# FSP.net
KiCad netlist of a schematic drawn in Altium Designer
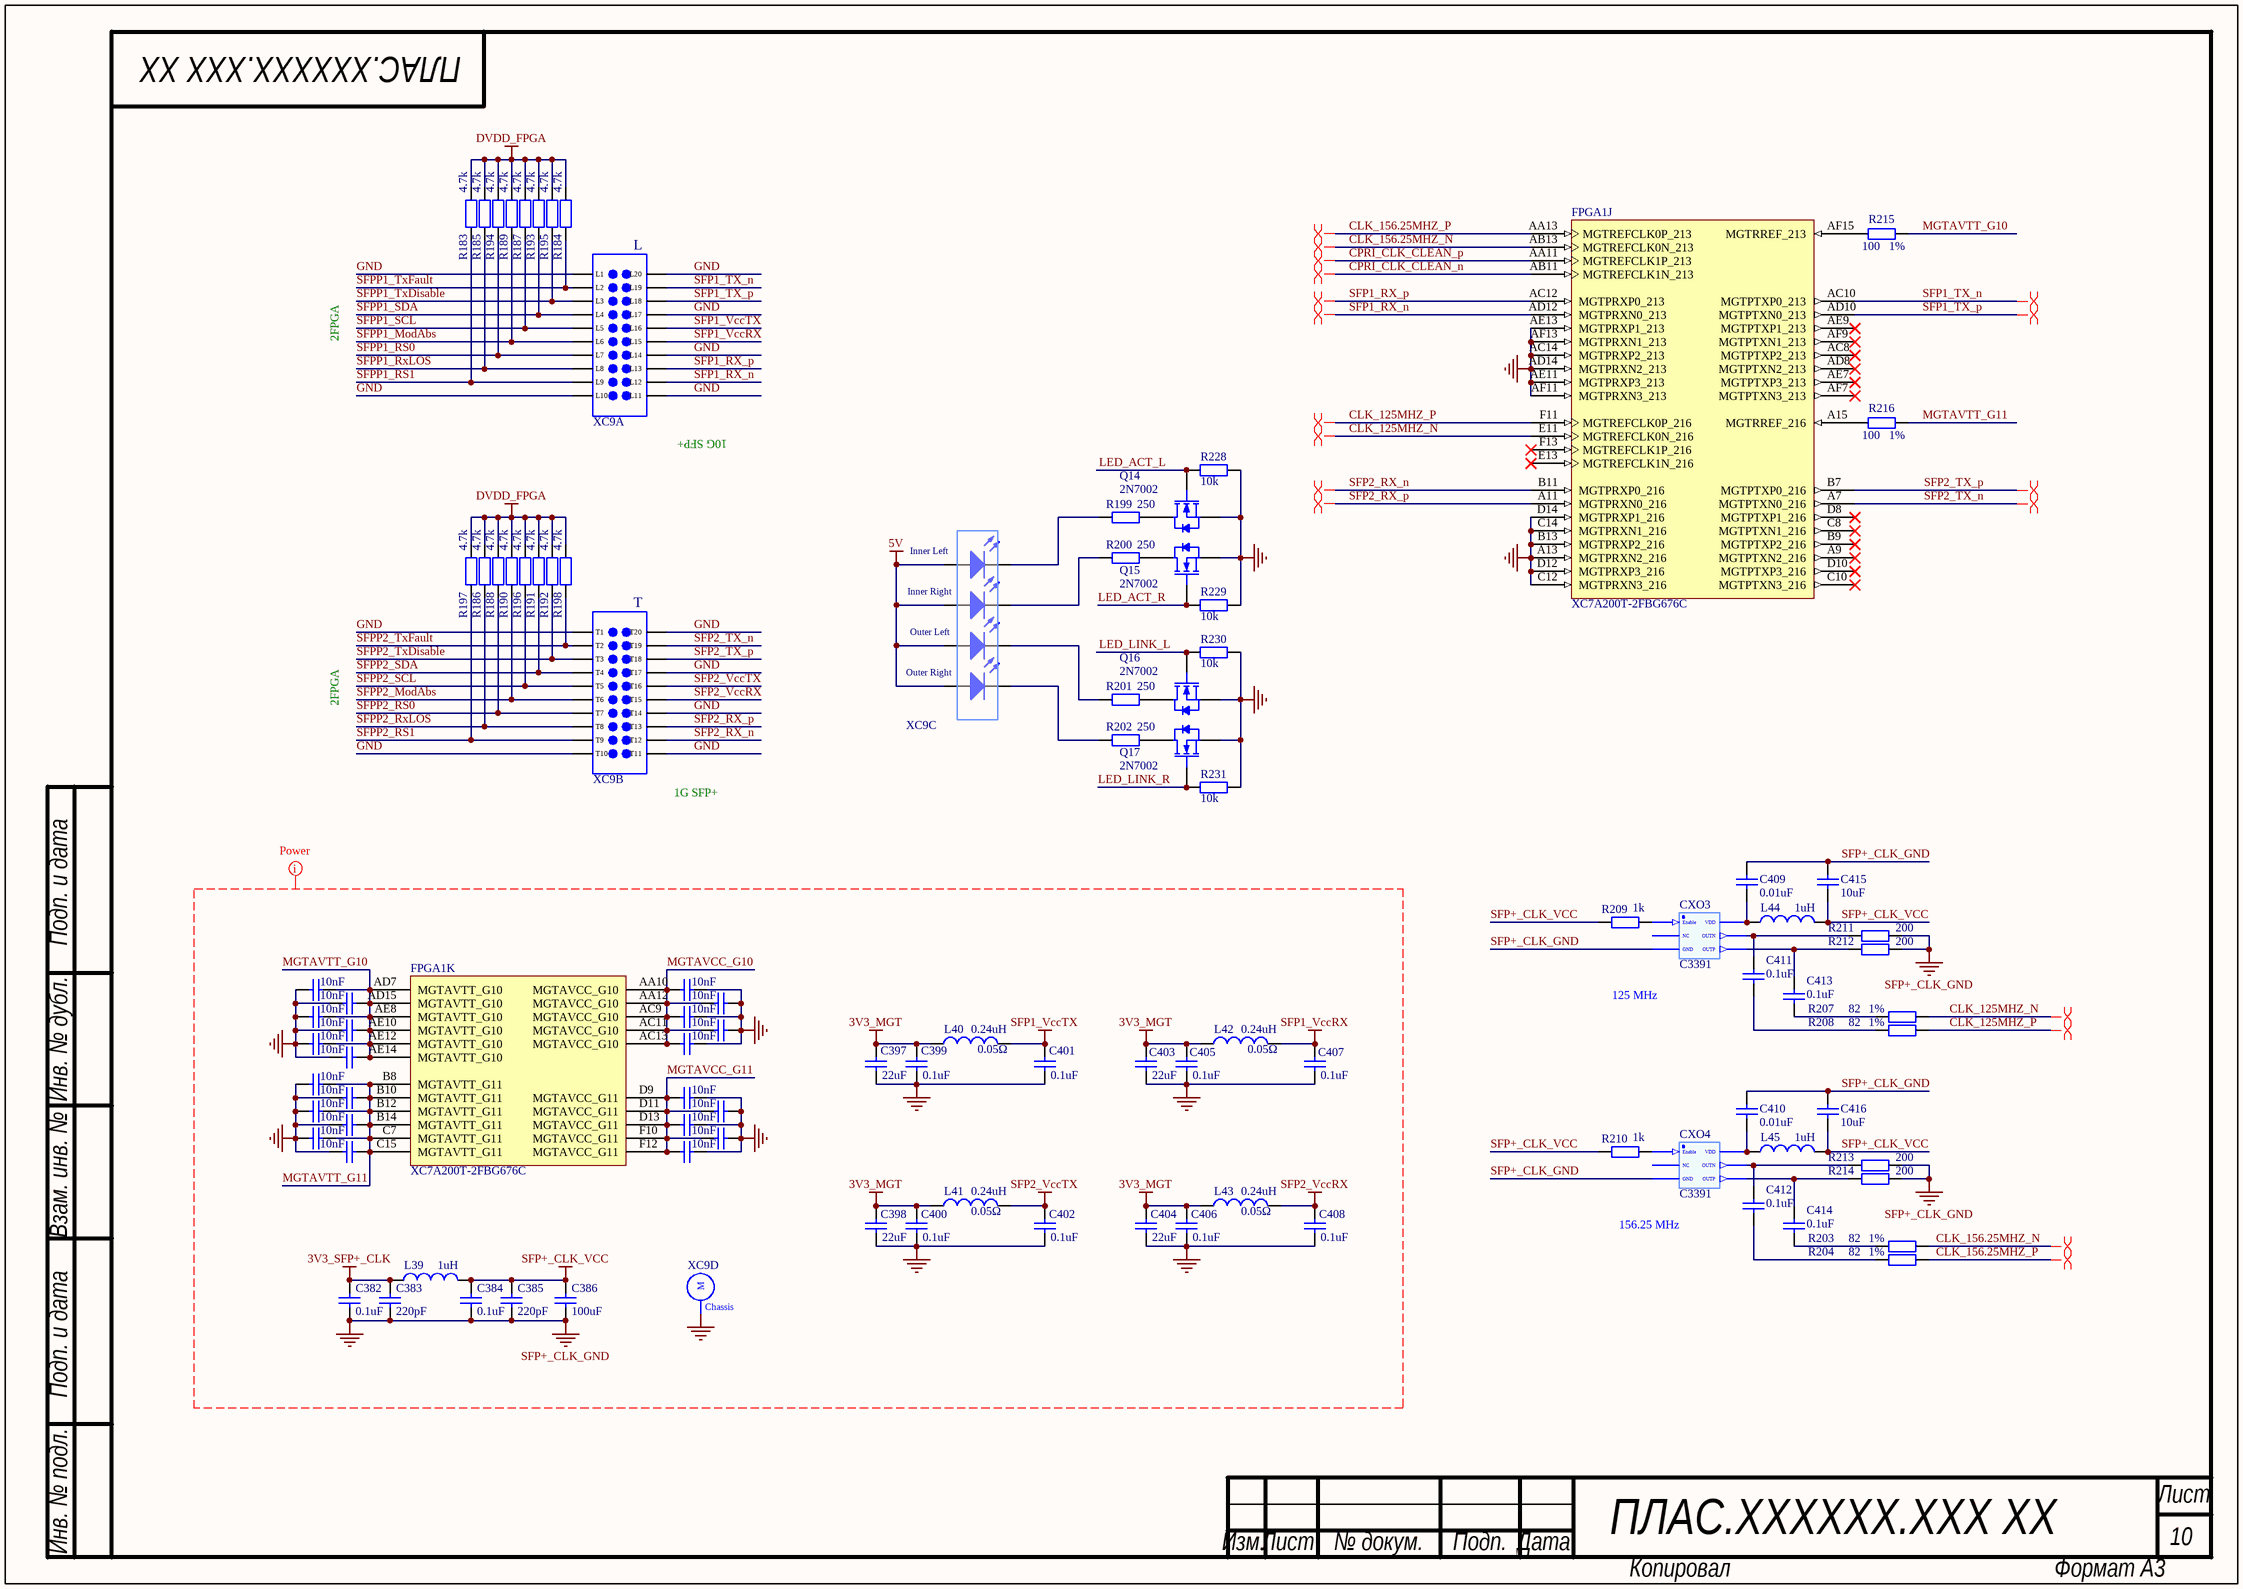
[diagram p0: FSP+.SchDoc]

(export (version "E")
  (design (tool "Eeschema 10.0.6"))
  (components
    (comp (ref "C370")
      (value "10nF")
      (footprint "С0402")
      (description "Cer Cap Small")
      (fields (field (name "MANUFACTURER") "Murata") (field (name "VOLTAGE") "25V"))
      (libsource (lib "") (part "Cer Cap_1"))
    )
    (comp (ref "C371")
      (value "10nF")
      (footprint "С0402")
      (description "Cer Cap Small")
      (fields (field (name "MANUFACTURER") "Murata") (field (name "VOLTAGE") "25V"))
      (libsource (lib "USRP2_Clone") (part "Cer Cap"))
    )
    (comp (ref "C372")
      (value "10nF")
      (footprint "С0402")
      (description "Cer Cap Small")
      (fields (field (name "MANUFACTURER") "Murata") (field (name "VOLTAGE") "25V"))
      (libsource (lib "USRP2_Clone") (part "Cer Cap"))
    )
    (comp (ref "C373")
      (value "10nF")
      (footprint "С0402")
      (description "Cer Cap Small")
      (fields (field (name "MANUFACTURER") "Murata") (field (name "VOLTAGE") "25V"))
      (libsource (lib "") (part "Cer Cap_1"))
    )
    (comp (ref "C374")
      (value "10nF")
      (footprint "С0402")
      (description "Cer Cap Small")
      (fields (field (name "MANUFACTURER") "Murata") (field (name "VOLTAGE") "25V"))
      (libsource (lib "") (part "Cer Cap_1"))
    )
    (comp (ref "C375")
      (value "10nF")
      (footprint "С0402")
      (description "Cer Cap Small")
      (fields (field (name "MANUFACTURER") "Murata") (field (name "VOLTAGE") "25V"))
      (libsource (lib "") (part "Cer Cap_1"))
    )
    (comp (ref "C376")
      (value "10nF")
      (footprint "С0402")
      (description "Cer Cap Small")
      (fields (field (name "MANUFACTURER") "Murata") (field (name "VOLTAGE") "25V"))
      (libsource (lib "") (part "Cer Cap_1"))
    )
    (comp (ref "C377")
      (value "10nF")
      (footprint "С0402")
      (description "Cer Cap Small")
      (fields (field (name "MANUFACTURER") "Murata") (field (name "VOLTAGE") "25V"))
      (libsource (lib "") (part "Cer Cap_1"))
    )
    (comp (ref "C378")
      (value "10nF")
      (footprint "С0402")
      (description "Cer Cap Small")
      (fields (field (name "MANUFACTURER") "Murata") (field (name "VOLTAGE") "25V"))
      (libsource (lib "") (part "Cer Cap_1"))
    )
    (comp (ref "C379")
      (value "10nF")
      (footprint "С0402")
      (description "Cer Cap Small")
      (fields (field (name "MANUFACTURER") "Murata") (field (name "VOLTAGE") "25V"))
      (libsource (lib "USRP2_Clone") (part "Cer Cap"))
    )
    (comp (ref "C380")
      (value "10nF")
      (footprint "С0402")
      (description "Cer Cap Small")
      (fields (field (name "MANUFACTURER") "Murata") (field (name "VOLTAGE") "25V"))
      (libsource (lib "USRP2_Clone") (part "Cer Cap"))
    )
    (comp (ref "C381")
      (value "10nF")
      (footprint "С0402")
      (description "Cer Cap Small")
      (fields (field (name "MANUFACTURER") "Murata") (field (name "VOLTAGE") "25V"))
      (libsource (lib "") (part "Cer Cap_1"))
    )
    (comp (ref "C382")
      (value "0.1uF")
      (footprint "C0603")
      (description "Cer Cap Small")
      (fields (field (name "MANUFACTURER") "Murata") (field (name "VOLTAGE") "16V"))
      (libsource (lib "USRP2_Clone") (part "Cer Cap"))
    )
    (comp (ref "C383")
      (value "220pF")
      (footprint "C0603")
      (description "Cer Cap Small")
      (fields (field (name "MANUFACTURER") "Murata") (field (name "VOLTAGE") "16V"))
      (libsource (lib "USRP2_Clone") (part "Cer Cap"))
    )
    (comp (ref "C384")
      (value "0.1uF")
      (footprint "C0603")
      (description "Cer Cap Small")
      (fields (field (name "MANUFACTURER") "Murata") (field (name "VOLTAGE") "16V"))
      (libsource (lib "USRP2_Clone") (part "Cer Cap"))
    )
    (comp (ref "C385")
      (value "220pF")
      (footprint "C0603")
      (description "Cer Cap Small")
      (fields (field (name "MANUFACTURER") "Murata") (field (name "VOLTAGE") "16V"))
      (libsource (lib "USRP2_Clone") (part "Cer Cap"))
    )
    (comp (ref "C386")
      (value "100uF")
      (footprint "C1210")
      (description "Cer Cap Large")
      (fields (field (name "MANUFACTURER") "Murata") (field (name "TOLERANCE") "20%"))
      (libsource (lib "USRP2_Clone") (part "Cap uF"))
    )
    (comp (ref "C387")
      (value "10nF")
      (footprint "С0402")
      (description "Cer Cap Small")
      (fields (field (name "MANUFACTURER") "Murata") (field (name "VOLTAGE") "25V"))
      (libsource (lib "") (part "Cer Cap_1"))
    )
    (comp (ref "C388")
      (value "10nF")
      (footprint "С0402")
      (description "Cer Cap Small")
      (fields (field (name "MANUFACTURER") "Murata") (field (name "VOLTAGE") "25V"))
      (libsource (lib "USRP2_Clone") (part "Cer Cap"))
    )
    (comp (ref "C389")
      (value "10nF")
      (footprint "С0402")
      (description "Cer Cap Small")
      (fields (field (name "MANUFACTURER") "Murata") (field (name "VOLTAGE") "25V"))
      (libsource (lib "") (part "Cer Cap_1"))
    )
    (comp (ref "C390")
      (value "10nF")
      (footprint "С0402")
      (description "Cer Cap Small")
      (fields (field (name "MANUFACTURER") "Murata") (field (name "VOLTAGE") "25V"))
      (libsource (lib "USRP2_Clone") (part "Cer Cap"))
    )
    (comp (ref "C391")
      (value "10nF")
      (footprint "С0402")
      (description "Cer Cap Small")
      (fields (field (name "MANUFACTURER") "Murata") (field (name "VOLTAGE") "25V"))
      (libsource (lib "USRP2_Clone") (part "Cer Cap"))
    )
    (comp (ref "C392")
      (value "10nF")
      (footprint "С0402")
      (description "Cer Cap Small")
      (fields (field (name "MANUFACTURER") "Murata") (field (name "VOLTAGE") "25V"))
      (libsource (lib "") (part "Cer Cap_1"))
    )
    (comp (ref "C393")
      (value "10nF")
      (footprint "С0402")
      (description "Cer Cap Small")
      (fields (field (name "MANUFACTURER") "Murata") (field (name "VOLTAGE") "25V"))
      (libsource (lib "USRP2_Clone") (part "Cer Cap"))
    )
    (comp (ref "C394")
      (value "10nF")
      (footprint "С0402")
      (description "Cer Cap Small")
      (fields (field (name "MANUFACTURER") "Murata") (field (name "VOLTAGE") "25V"))
      (libsource (lib "USRP2_Clone") (part "Cer Cap"))
    )
    (comp (ref "C395")
      (value "10nF")
      (footprint "С0402")
      (description "Cer Cap Small")
      (fields (field (name "MANUFACTURER") "Murata") (field (name "VOLTAGE") "25V"))
      (libsource (lib "USRP2_Clone") (part "Cer Cap"))
    )
    (comp (ref "C396")
      (value "10nF")
      (footprint "С0402")
      (description "Cer Cap Small")
      (fields (field (name "MANUFACTURER") "Murata") (field (name "VOLTAGE") "25V"))
      (libsource (lib "USRP2_Clone") (part "Cer Cap"))
    )
    (comp (ref "C397")
      (value "22uF")
      (footprint "C0805")
      (description "Cer Cap Small")
      (fields (field (name "MANUFACTURER") "Murata") (field (name "VOLTAGE") "6.3V"))
      (libsource (lib "") (part "Cer Cap_1"))
    )
    (comp (ref "C398")
      (value "22uF")
      (footprint "C0805")
      (description "Cer Cap Small")
      (fields (field (name "MANUFACTURER") "Murata") (field (name "VOLTAGE") "6.3V"))
      (libsource (lib "USRP2_Clone") (part "Cer Cap"))
    )
    (comp (ref "C399")
      (value "0.1uF")
      (footprint "C0805")
      (description "Cer Cap Small")
      (fields (field (name "MANUFACTURER") "Murata") (field (name "VOLTAGE") "50V"))
      (libsource (lib "USRP2_Clone") (part "Cer Cap"))
    )
    (comp (ref "C400")
      (value "0.1uF")
      (footprint "C0805")
      (description "Cer Cap Small")
      (fields (field (name "MANUFACTURER") "Murata") (field (name "VOLTAGE") "50V"))
      (libsource (lib "") (part "Cer Cap_1"))
    )
    (comp (ref "C401")
      (value "0.1uF")
      (footprint "C0805")
      (description "Cer Cap Small")
      (fields (field (name "MANUFACTURER") "Murata") (field (name "VOLTAGE") "50V"))
      (libsource (lib "USRP2_Clone") (part "Cer Cap"))
    )
    (comp (ref "C402")
      (value "0.1uF")
      (footprint "C0805")
      (description "Cer Cap Small")
      (fields (field (name "MANUFACTURER") "Murata") (field (name "VOLTAGE") "50V"))
      (libsource (lib "USRP2_Clone") (part "Cer Cap"))
    )
    (comp (ref "C403")
      (value "22uF")
      (footprint "C0805")
      (description "Cer Cap Small")
      (fields (field (name "MANUFACTURER") "Murata") (field (name "VOLTAGE") "6.3V"))
      (libsource (lib "") (part "Cer Cap_1"))
    )
    (comp (ref "C404")
      (value "22uF")
      (footprint "C0805")
      (description "Cer Cap Small")
      (fields (field (name "MANUFACTURER") "Murata") (field (name "VOLTAGE") "6.3V"))
      (libsource (lib "") (part "Cer Cap_1"))
    )
    (comp (ref "C405")
      (value "0.1uF")
      (footprint "C0805")
      (description "Cer Cap Small")
      (fields (field (name "MANUFACTURER") "Murata") (field (name "VOLTAGE") "50V"))
      (libsource (lib "USRP2_Clone") (part "Cer Cap"))
    )
    (comp (ref "C406")
      (value "0.1uF")
      (footprint "C0805")
      (description "Cer Cap Small")
      (fields (field (name "MANUFACTURER") "Murata") (field (name "VOLTAGE") "50V"))
      (libsource (lib "USRP2_Clone") (part "Cer Cap"))
    )
    (comp (ref "C407")
      (value "0.1uF")
      (footprint "C0805")
      (description "Cer Cap Small")
      (fields (field (name "MANUFACTURER") "Murata") (field (name "VOLTAGE") "50V"))
      (libsource (lib "USRP2_Clone") (part "Cer Cap"))
    )
    (comp (ref "C408")
      (value "0.1uF")
      (footprint "C0805")
      (description "Cer Cap Small")
      (fields (field (name "MANUFACTURER") "Murata") (field (name "VOLTAGE") "50V"))
      (libsource (lib "USRP2_Clone") (part "Cer Cap"))
    )
    (comp (ref "C409")
      (value "0.01uF")
      (footprint "C0603")
      (description "Cer Cap Small")
      (fields (field (name "MANUFACTURER") "Murata") (field (name "VOLTAGE") "50V"))
      (libsource (lib "") (part "Cer Cap_1"))
    )
    (comp (ref "C410")
      (value "0.01uF")
      (footprint "C0603")
      (description "Cer Cap Small")
      (fields (field (name "MANUFACTURER") "Murata") (field (name "VOLTAGE") "50V"))
      (libsource (lib "") (part "Cer Cap_1"))
    )
    (comp (ref "C411")
      (value "0.1uF")
      (footprint "С0402")
      (description "Cer Cap Small")
      (fields (field (name "MANUFACTURER") "Murata") (field (name "VOLTAGE") "16V"))
      (libsource (lib "USRP2_Clone") (part "Cer Cap"))
    )
    (comp (ref "C412")
      (value "0.1uF")
      (footprint "С0402")
      (description "Cer Cap Small")
      (fields (field (name "MANUFACTURER") "Murata") (field (name "VOLTAGE") "16V"))
      (libsource (lib "USRP2_Clone") (part "Cer Cap"))
    )
    (comp (ref "C413")
      (value "0.1uF")
      (footprint "С0402")
      (description "Cer Cap Small")
      (fields (field (name "MANUFACTURER") "Murata") (field (name "VOLTAGE") "16V"))
      (libsource (lib "USRP2_Clone") (part "Cer Cap"))
    )
    (comp (ref "C414")
      (value "0.1uF")
      (footprint "С0402")
      (description "Cer Cap Small")
      (fields (field (name "MANUFACTURER") "Murata") (field (name "VOLTAGE") "16V"))
      (libsource (lib "USRP2_Clone") (part "Cer Cap"))
    )
    (comp (ref "C415")
      (value "10uF")
      (footprint "C0603")
      (description "Cer Cap Small")
      (fields (field (name "MANUFACTURER") "Murata") (field (name "VOLTAGE") "6.3V"))
      (libsource (lib "") (part "Cer Cap_1"))
    )
    (comp (ref "C416")
      (value "10uF")
      (footprint "C0603")
      (description "Cer Cap Small")
      (fields (field (name "MANUFACTURER") "Murata") (field (name "VOLTAGE") "6.3V"))
      (libsource (lib "") (part "Cer Cap_1"))
    )
    (comp (ref "CXO3")
      (value "C3391")
      (footprint "5x7 CXO LVPECL")
      (description "Crystal Oscillator")
      (fields
        (field (name "VOLTAGE") "3.3V ±0.3V")
        (field (name "MANUFACTURER") "Crystek")
        (field (name "FREQUENCY") "125 MHz")
      )
      (libsource (lib "USRP2_Clone") (part "5x7 LVPECL CXO"))
    )
    (comp (ref "CXO4")
      (value "C3391")
      (footprint "5x7 CXO LVPECL")
      (description "Crystal Oscillator")
      (fields
        (field (name "VOLTAGE") "3.3V ±0.3V")
        (field (name "MANUFACTURER") "Crystek")
        (field (name "FREQUENCY") "156.25 MHz")
      )
      (libsource (lib "USRP2_Clone") (part "5x7 LVPECL CXO"))
    )
    (comp (ref "FPGA1")
      (value "XC7A200T-2FBG676C")
      (footprint "FGG676")
      (description "Artix-7 FPGA, 400 User I/Os, 8 GTP, 676-Ball BGA, Speed Grade 2, Commercial Grade, Pb-Free")
      (fields (field (name "GENERIC PART NUMBER") "XC7A200T") (field (name "MANUFACTURER") "Xilinx"))
      (libsource (lib "USRP2_Clone") (part "XC7A200T-2FBG676C"))
    )
    (comp (ref "L39")
      (value "1uH")
      (footprint "L1210_Murata")
      (description "Inductor_Power_Lines")
      (fields (field (name "TOLERANCE") "5%") (field (name "MANUFACTURER") "Murata"))
      (libsource (lib "") (part "Inductor_LF_1"))
    )
    (comp (ref "L40")
      (value "0.24uH")
      (footprint "L0805_Murata_LQG")
      (description "Inductor_Power_Lines")
      (fields
        (field (name "TOLERANCE") "±20%")
        (field (name "MANUFACTURER") "Murata")
        (field (name "DCR") "0.05Ω")
      )
      (libsource (lib "USRP2_Clone") (part "Inductor_LF"))
    )
    (comp (ref "L41")
      (value "0.24uH")
      (footprint "L0805_Murata_LQG")
      (description "Inductor_Power_Lines")
      (fields
        (field (name "TOLERANCE") "±20%")
        (field (name "MANUFACTURER") "Murata")
        (field (name "DCR") "0.05Ω")
      )
      (libsource (lib "") (part "Inductor_LF_1"))
    )
    (comp (ref "L42")
      (value "0.24uH")
      (footprint "L0805_Murata_LQG")
      (description "Inductor_Power_Lines")
      (fields
        (field (name "TOLERANCE") "±20%")
        (field (name "MANUFACTURER") "Murata")
        (field (name "DCR") "0.05Ω")
      )
      (libsource (lib "USRP2_Clone") (part "Inductor_LF"))
    )
    (comp (ref "L43")
      (value "0.24uH")
      (footprint "L0805_Murata_LQG")
      (description "Inductor_Power_Lines")
      (fields
        (field (name "TOLERANCE") "±20%")
        (field (name "MANUFACTURER") "Murata")
        (field (name "DCR") "0.05Ω")
      )
      (libsource (lib "") (part "Inductor_LF_1"))
    )
    (comp (ref "L44")
      (value "1uH")
      (footprint "L1206_Murata")
      (description "Inductor_Power_Lines")
      (fields (field (name "TOLERANCE") "5%") (field (name "MANUFACTURER") "Murata"))
      (libsource (lib "") (part "Inductor_LF_1"))
    )
    (comp (ref "L45")
      (value "1uH")
      (footprint "L1206_Murata")
      (description "Inductor_Power_Lines")
      (fields (field (name "TOLERANCE") "5%") (field (name "MANUFACTURER") "Murata"))
      (libsource (lib "") (part "Inductor_LF_1"))
    )
    (comp (ref "Q14")
      (value "2N7002")
      (footprint "SOT-23")
      (description "N-Channel MOSFET 2N7002")
      (fields (field (name "VOLTAGE") "60V"))
      (libsource (lib "USRP2_Clone") (part "2N7002"))
    )
    (comp (ref "Q15")
      (value "2N7002")
      (footprint "SOT-23")
      (description "N-Channel MOSFET 2N7002")
      (fields (field (name "VOLTAGE") "60V"))
      (libsource (lib "USRP2_Clone") (part "2N7002"))
    )
    (comp (ref "Q16")
      (value "2N7002")
      (footprint "SOT-23")
      (description "N-Channel MOSFET 2N7002")
      (fields (field (name "VOLTAGE") "60V"))
      (libsource (lib "USRP2_Clone") (part "2N7002"))
    )
    (comp (ref "Q17")
      (value "2N7002")
      (footprint "SOT-23")
      (description "N-Channel MOSFET 2N7002")
      (fields (field (name "VOLTAGE") "60V"))
      (libsource (lib "USRP2_Clone") (part "2N7002"))
    )
    (comp (ref "R183")
      (value "4.7k")
      (footprint "R0402")
      (description "Resistor")
      (fields (field (name "TOLERANCE") "5%") (field (name "POWER") "0.062 Wt"))
      (libsource (lib "") (part "Res_1"))
    )
    (comp (ref "R184")
      (value "4.7k")
      (footprint "R0402")
      (description "Resistor")
      (fields (field (name "TOLERANCE") "5%") (field (name "POWER") "0.062 Wt"))
      (libsource (lib "") (part "Res_1"))
    )
    (comp (ref "R185")
      (value "4.7k")
      (footprint "R0402")
      (description "Resistor")
      (fields (field (name "TOLERANCE") "5%") (field (name "POWER") "0.062 Wt"))
      (libsource (lib "") (part "Res_1"))
    )
    (comp (ref "R186")
      (value "4.7k")
      (footprint "R0402")
      (description "Resistor")
      (fields (field (name "TOLERANCE") "5%") (field (name "POWER") "0.062 Wt"))
      (libsource (lib "") (part "Res_1"))
    )
    (comp (ref "R187")
      (value "4.7k")
      (footprint "R0402")
      (description "Resistor")
      (fields (field (name "TOLERANCE") "5%") (field (name "POWER") "0.062 Wt"))
      (libsource (lib "") (part "Res_1"))
    )
    (comp (ref "R188")
      (value "4.7k")
      (footprint "R0402")
      (description "Resistor")
      (fields (field (name "TOLERANCE") "5%") (field (name "POWER") "0.062 Wt"))
      (libsource (lib "") (part "Res_1"))
    )
    (comp (ref "R189")
      (value "4.7k")
      (footprint "R0402")
      (description "Resistor")
      (fields (field (name "TOLERANCE") "5%") (field (name "POWER") "0.062 Wt"))
      (libsource (lib "") (part "Res_1"))
    )
    (comp (ref "R190")
      (value "4.7k")
      (footprint "R0402")
      (description "Resistor")
      (fields (field (name "TOLERANCE") "5%") (field (name "POWER") "0.062 Wt"))
      (libsource (lib "") (part "Res_1"))
    )
    (comp (ref "R191")
      (value "4.7k")
      (footprint "R0402")
      (description "Resistor")
      (fields (field (name "TOLERANCE") "5%") (field (name "POWER") "0.062 Wt"))
      (libsource (lib "") (part "Res_1"))
    )
    (comp (ref "R192")
      (value "4.7k")
      (footprint "R0402")
      (description "Resistor")
      (fields (field (name "TOLERANCE") "5%") (field (name "POWER") "0.062 Wt"))
      (libsource (lib "") (part "Res_1"))
    )
    (comp (ref "R193")
      (value "4.7k")
      (footprint "R0402")
      (description "Resistor")
      (fields (field (name "TOLERANCE") "5%") (field (name "POWER") "0.062 Wt"))
      (libsource (lib "") (part "Res_1"))
    )
    (comp (ref "R194")
      (value "4.7k")
      (footprint "R0402")
      (description "Resistor")
      (fields (field (name "TOLERANCE") "5%") (field (name "POWER") "0.062 Wt"))
      (libsource (lib "") (part "Res_1"))
    )
    (comp (ref "R195")
      (value "4.7k")
      (footprint "R0402")
      (description "Resistor")
      (fields (field (name "TOLERANCE") "5%") (field (name "POWER") "0.062 Wt"))
      (libsource (lib "") (part "Res_1"))
    )
    (comp (ref "R196")
      (value "4.7k")
      (footprint "R0402")
      (description "Resistor")
      (fields (field (name "TOLERANCE") "5%") (field (name "POWER") "0.062 Wt"))
      (libsource (lib "") (part "Res_1"))
    )
    (comp (ref "R197")
      (value "4.7k")
      (footprint "R0402")
      (description "Resistor")
      (fields (field (name "TOLERANCE") "5%") (field (name "POWER") "0.062 Wt"))
      (libsource (lib "") (part "Res_1"))
    )
    (comp (ref "R198")
      (value "4.7k")
      (footprint "R0402")
      (description "Resistor")
      (fields (field (name "TOLERANCE") "5%") (field (name "POWER") "0.062 Wt"))
      (libsource (lib "") (part "Res_1"))
    )
    (comp (ref "R199")
      (value "250")
      (footprint "R0805")
      (description "Resistor")
      (fields (field (name "TOLERANCE") "5%") (field (name "POWER") "0.125W"))
      (libsource (lib "") (part "Res_3"))
    )
    (comp (ref "R200")
      (value "250")
      (footprint "R0805")
      (description "Resistor")
      (fields (field (name "TOLERANCE") "5%") (field (name "POWER") "0.125W"))
      (libsource (lib "USRP2_Clone") (part "Res"))
    )
    (comp (ref "R201")
      (value "250")
      (footprint "R0805")
      (description "Resistor")
      (fields (field (name "TOLERANCE") "5%") (field (name "POWER") "0.125W"))
      (libsource (lib "") (part "Res_3"))
    )
    (comp (ref "R202")
      (value "250")
      (footprint "R0805")
      (description "Resistor")
      (fields (field (name "TOLERANCE") "5%") (field (name "POWER") "0.125W"))
      (libsource (lib "USRP2_Clone") (part "Res"))
    )
    (comp (ref "R203")
      (value "82")
      (footprint "R0402")
      (description "Resistor")
      (fields
        (field (name "TOLERANCE") "1%")
        (field (name "POWER") "0.062 Wt")
        (field (name "Comment") "Res")
      )
      (libsource (lib "") (part "Res_2"))
    )
    (comp (ref "R204")
      (value "82")
      (footprint "R0402")
      (description "Resistor")
      (fields
        (field (name "TOLERANCE") "1%")
        (field (name "POWER") "0.062 Wt")
        (field (name "Comment") "Res")
      )
      (libsource (lib "USRP2_Clone") (part "Res"))
    )
    (comp (ref "R207")
      (value "82")
      (footprint "R0402")
      (description "Resistor")
      (fields
        (field (name "TOLERANCE") "1%")
        (field (name "POWER") "0.062 Wt")
        (field (name "Comment") "Res")
      )
      (libsource (lib "") (part "Res_2"))
    )
    (comp (ref "R208")
      (value "82")
      (footprint "R0402")
      (description "Resistor")
      (fields
        (field (name "TOLERANCE") "1%")
        (field (name "POWER") "0.062 Wt")
        (field (name "Comment") "Res")
      )
      (libsource (lib "USRP2_Clone") (part "Res"))
    )
    (comp (ref "R209")
      (value "1k")
      (footprint "R0402")
      (description "Resistor")
      (fields (field (name "TOLERANCE") "5%") (field (name "POWER") "0.062 Wt"))
      (libsource (lib "USRP2_Clone") (part "Res"))
    )
    (comp (ref "R210")
      (value "1k")
      (footprint "R0402")
      (description "Resistor")
      (fields (field (name "TOLERANCE") "5%") (field (name "POWER") "0.062 Wt"))
      (libsource (lib "USRP2_Clone") (part "Res"))
    )
    (comp (ref "R211")
      (value "200")
      (footprint "R0402")
      (description "Resistor")
      (fields (field (name "TOLERANCE") "5%") (field (name "POWER") "0.062 Wt"))
      (libsource (lib "") (part "Res_4"))
    )
    (comp (ref "R212")
      (value "200")
      (footprint "R0402")
      (description "Resistor")
      (fields (field (name "TOLERANCE") "5%") (field (name "POWER") "0.062 Wt"))
      (libsource (lib "") (part "Res_4"))
    )
    (comp (ref "R213")
      (value "200")
      (footprint "R0402")
      (description "Resistor")
      (fields (field (name "TOLERANCE") "5%") (field (name "POWER") "0.062 Wt"))
      (libsource (lib "") (part "Res_4"))
    )
    (comp (ref "R214")
      (value "200")
      (footprint "R0402")
      (description "Resistor")
      (fields (field (name "TOLERANCE") "5%") (field (name "POWER") "0.062 Wt"))
      (libsource (lib "") (part "Res_4"))
    )
    (comp (ref "R215")
      (value "100")
      (footprint "R0603")
      (description "Resistor")
      (fields
        (field (name "TOLERANCE") "1%")
        (field (name "POWER") "0.062 Wt")
        (field (name "Comment") "Res")
      )
      (libsource (lib "") (part "Res_3"))
    )
    (comp (ref "R216")
      (value "100")
      (footprint "R0603")
      (description "Resistor")
      (fields
        (field (name "TOLERANCE") "1%")
        (field (name "POWER") "0.062 Wt")
        (field (name "Comment") "Res")
      )
      (libsource (lib "") (part "Res_3"))
    )
    (comp (ref "R228")
      (value "10k")
      (footprint "R0402")
      (description "Resistor")
      (fields (field (name "TOLERANCE") "5%") (field (name "POWER") "0.062 Wt"))
      (libsource (lib "") (part "Res_1"))
    )
    (comp (ref "R229")
      (value "10k")
      (footprint "R0402")
      (description "Resistor")
      (fields (field (name "TOLERANCE") "5%") (field (name "POWER") "0.062 Wt"))
      (libsource (lib "") (part "Res_1"))
    )
    (comp (ref "R230")
      (value "10k")
      (footprint "R0402")
      (description "Resistor")
      (fields (field (name "TOLERANCE") "5%") (field (name "POWER") "0.062 Wt"))
      (libsource (lib "") (part "Res_1"))
    )
    (comp (ref "R231")
      (value "10k")
      (footprint "R0402")
      (description "Resistor")
      (fields (field (name "TOLERANCE") "5%") (field (name "POWER") "0.062 Wt"))
      (libsource (lib "") (part "Res_1"))
    )
    (comp (ref "XC9")
      (value "SFP+")
      (footprint "SFP+ Light Pipe")
      (description "SFP+ 1 by 2 Connector")
      (fields (field (name "MANUFACTURER") "Molex"))
      (libsource (lib "") (part "SFP+_2X1_1"))
    )
  )
  (nets
    (net (code "1") (name "/CLK_125MHZ_N") (class "Default")
      (node (ref "FPGA1") (pin "E11") (pinfunction "MGTREFCLK0N_216_E11") (pintype "input"))
      (node (ref "R207") (pin "2") (pinfunction "2_2") (pintype "passive"))
    )
    (net (code "2") (name "/CLK_125MHZ_P") (class "Default")
      (node (ref "FPGA1") (pin "F11") (pinfunction "MGTREFCLK0P_216_F11") (pintype "input"))
      (node (ref "R208") (pin "2") (pinfunction "2_2") (pintype "passive"))
    )
    (net (code "3") (name "/CLK_156.25MHZ_N") (class "Default")
      (node (ref "FPGA1") (pin "AB13") (pinfunction "MGTREFCLK0N_213_AB13") (pintype "input"))
      (node (ref "R203") (pin "2") (pinfunction "2_2") (pintype "passive"))
    )
    (net (code "4") (name "/CLK_156.25MHZ_P") (class "Default")
      (node (ref "FPGA1") (pin "AA13") (pinfunction "MGTREFCLK0P_213_AA13") (pintype "input"))
      (node (ref "R204") (pin "2") (pinfunction "2_2") (pintype "passive"))
    )
    (net (code "5") (name "/CPRI_CLK_CLEAN_n") (class "Default")
      (node (ref "FPGA1") (pin "AB11") (pinfunction "MGTREFCLK1N_213_AB11") (pintype "input"))
    )
    (net (code "6") (name "/CPRI_CLK_CLEAN_p") (class "Default")
      (node (ref "FPGA1") (pin "AA11") (pinfunction "MGTREFCLK1P_213_AA11") (pintype "input"))
    )
    (net (code "7") (name "/LED_ACT_L") (class "Default")
      (node (ref "Q14") (pin "1") (pinfunction "G_1") (pintype "passive"))
      (node (ref "R228") (pin "1") (pinfunction "1_1") (pintype "passive"))
    )
    (net (code "8") (name "/LED_ACT_R") (class "Default")
      (node (ref "Q15") (pin "1") (pinfunction "G_1") (pintype "passive"))
      (node (ref "R229") (pin "1") (pinfunction "1_1") (pintype "passive"))
    )
    (net (code "9") (name "/LED_LINK_L") (class "Default")
      (node (ref "Q16") (pin "1") (pinfunction "G_1") (pintype "passive"))
      (node (ref "R230") (pin "1") (pinfunction "1_1") (pintype "passive"))
    )
    (net (code "10") (name "/LED_LINK_R") (class "Default")
      (node (ref "Q17") (pin "1") (pinfunction "G_1") (pintype "passive"))
      (node (ref "R231") (pin "1") (pinfunction "1_1") (pintype "passive"))
    )
    (net (code "11") (name "/MGTAVCC_G10") (class "Default")
      (node (ref "C387") (pin "2") (pinfunction "2_2") (pintype "passive"))
      (node (ref "C388") (pin "1") (pinfunction "1_1") (pintype "passive"))
      (node (ref "C389") (pin "2") (pinfunction "2_2") (pintype "passive"))
      (node (ref "C393") (pin "1") (pinfunction "1_1") (pintype "passive"))
      (node (ref "C394") (pin "1") (pinfunction "1_1") (pintype "passive"))
      (node (ref "FPGA1") (pin "AA10") (pinfunction "MGTAVCC_G10_AA10") (pintype "power_in"))
      (node (ref "FPGA1") (pin "AA12") (pinfunction "MGTAVCC_G10_AA12") (pintype "power_in"))
      (node (ref "FPGA1") (pin "AC11") (pinfunction "MGTAVCC_G10_AC11") (pintype "power_in"))
      (node (ref "FPGA1") (pin "AC13") (pinfunction "MGTAVCC_G10_AC13") (pintype "power_in"))
      (node (ref "FPGA1") (pin "AC9") (pinfunction "MGTAVCC_G10_AC9") (pintype "power_in"))
    )
    (net (code "12") (name "/MGTAVCC_G11") (class "Default")
      (node (ref "C390") (pin "1") (pinfunction "1_1") (pintype "passive"))
      (node (ref "C391") (pin "1") (pinfunction "1_1") (pintype "passive"))
      (node (ref "C392") (pin "2") (pinfunction "2_2") (pintype "passive"))
      (node (ref "C395") (pin "1") (pinfunction "1_1") (pintype "passive"))
      (node (ref "C396") (pin "1") (pinfunction "1_1") (pintype "passive"))
      (node (ref "FPGA1") (pin "D11") (pinfunction "MGTAVCC_G11_D11") (pintype "power_in"))
      (node (ref "FPGA1") (pin "D13") (pinfunction "MGTAVCC_G11_D13") (pintype "power_in"))
      (node (ref "FPGA1") (pin "D9") (pinfunction "MGTAVCC_G11_D9") (pintype "power_in"))
      (node (ref "FPGA1") (pin "F10") (pinfunction "MGTAVCC_G11_F10") (pintype "power_in"))
      (node (ref "FPGA1") (pin "F12") (pinfunction "MGTAVCC_G11_F12") (pintype "power_in"))
    )
    (net (code "13") (name "/MGTAVTT_G10") (class "Default")
      (node (ref "C370") (pin "1") (pinfunction "1_1") (pintype "passive"))
      (node (ref "C371") (pin "2") (pinfunction "2_2") (pintype "passive"))
      (node (ref "C372") (pin "2") (pinfunction "2_2") (pintype "passive"))
      (node (ref "C376") (pin "1") (pinfunction "1_1") (pintype "passive"))
      (node (ref "C377") (pin "1") (pinfunction "1_1") (pintype "passive"))
      (node (ref "C378") (pin "1") (pinfunction "1_1") (pintype "passive"))
      (node (ref "FPGA1") (pin "AD15") (pinfunction "MGTAVTT_G10_AD15") (pintype "power_in"))
      (node (ref "FPGA1") (pin "AD7") (pinfunction "MGTAVTT_G10_AD7") (pintype "power_in"))
      (node (ref "FPGA1") (pin "AE10") (pinfunction "MGTAVTT_G10_AE10") (pintype "power_in"))
      (node (ref "FPGA1") (pin "AE12") (pinfunction "MGTAVTT_G10_AE12") (pintype "power_in"))
      (node (ref "FPGA1") (pin "AE14") (pinfunction "MGTAVTT_G10_AE14") (pintype "power_in"))
      (node (ref "FPGA1") (pin "AE8") (pinfunction "MGTAVTT_G10_AE8") (pintype "power_in"))
      (node (ref "R215") (pin "1") (pinfunction "1_1") (pintype "passive"))
    )
    (net (code "14") (name "/MGTAVTT_G11") (class "Default")
      (node (ref "C373") (pin "1") (pinfunction "1_1") (pintype "passive"))
      (node (ref "C374") (pin "1") (pinfunction "1_1") (pintype "passive"))
      (node (ref "C375") (pin "1") (pinfunction "1_1") (pintype "passive"))
      (node (ref "C379") (pin "2") (pinfunction "2_2") (pintype "passive"))
      (node (ref "C380") (pin "2") (pinfunction "2_2") (pintype "passive"))
      (node (ref "C381") (pin "1") (pinfunction "1_1") (pintype "passive"))
      (node (ref "FPGA1") (pin "B10") (pinfunction "MGTAVTT_G11_B10") (pintype "power_in"))
      (node (ref "FPGA1") (pin "B12") (pinfunction "MGTAVTT_G11_B12") (pintype "power_in"))
      (node (ref "FPGA1") (pin "B14") (pinfunction "MGTAVTT_G11_B14") (pintype "power_in"))
      (node (ref "FPGA1") (pin "B8") (pinfunction "MGTAVTT_G11_B8") (pintype "power_in"))
      (node (ref "FPGA1") (pin "C15") (pinfunction "MGTAVTT_G11_C15") (pintype "power_in"))
      (node (ref "FPGA1") (pin "C7") (pinfunction "MGTAVTT_G11_C7") (pintype "power_in"))
      (node (ref "R216") (pin "1") (pinfunction "1_1") (pintype "passive"))
    )
    (net (code "15") (name "/SFP1_RX_n") (class "Default")
      (node (ref "FPGA1") (pin "AD12") (pinfunction "MGTPRXN0_213_AD12") (pintype "input"))
      (node (ref "XC9") (pin "L12") (pinfunction "L12_L12") (pintype "passive"))
    )
    (net (code "16") (name "/SFP1_RX_p") (class "Default")
      (node (ref "FPGA1") (pin "AC12") (pinfunction "MGTPRXP0_213_AC12") (pintype "input"))
      (node (ref "XC9") (pin "L13") (pinfunction "L13_L13") (pintype "passive"))
    )
    (net (code "17") (name "/SFP1_TX_n") (class "Default")
      (node (ref "FPGA1") (pin "AC10") (pinfunction "MGTPTXP0_213_AC10") (pintype "output"))
      (node (ref "XC9") (pin "L19") (pinfunction "L19_L19") (pintype "passive"))
    )
    (net (code "18") (name "/SFP1_TX_p") (class "Default")
      (node (ref "FPGA1") (pin "AD10") (pinfunction "MGTPTXN0_213_AD10") (pintype "output"))
      (node (ref "XC9") (pin "L18") (pinfunction "L18_L18") (pintype "passive"))
    )
    (net (code "19") (name "/SFP2_RX_n") (class "Default")
      (node (ref "FPGA1") (pin "B11") (pinfunction "MGTPRXP0_216_B11") (pintype "input"))
      (node (ref "XC9") (pin "T12") (pinfunction "T12_T12") (pintype "passive"))
    )
    (net (code "20") (name "/SFP2_RX_p") (class "Default")
      (node (ref "FPGA1") (pin "A11") (pinfunction "MGTPRXN0_216_A11") (pintype "input"))
      (node (ref "XC9") (pin "T13") (pinfunction "T13_T13") (pintype "passive"))
    )
    (net (code "21") (name "/SFP2_TX_n") (class "Default")
      (node (ref "FPGA1") (pin "A7") (pinfunction "MGTPTXN0_216_A7") (pintype "output"))
      (node (ref "XC9") (pin "T19") (pinfunction "T19_T19") (pintype "passive"))
    )
    (net (code "22") (name "/SFP2_TX_p") (class "Default")
      (node (ref "FPGA1") (pin "B7") (pinfunction "MGTPTXP0_216_B7") (pintype "output"))
      (node (ref "XC9") (pin "T18") (pinfunction "T18_T18") (pintype "passive"))
    )
    (net (code "23") (name "/SFPP1_ModAbs") (class "Default")
      (node (ref "R189") (pin "1") (pinfunction "1_1") (pintype "passive"))
      (node (ref "XC9") (pin "L6") (pinfunction "L6_L6") (pintype "passive"))
    )
    (net (code "24") (name "/SFPP1_RS0") (class "Default")
      (node (ref "R194") (pin "1") (pinfunction "1_1") (pintype "passive"))
      (node (ref "XC9") (pin "L7") (pinfunction "L7_L7") (pintype "passive"))
    )
    (net (code "25") (name "/SFPP1_RS1") (class "Default")
      (node (ref "R183") (pin "1") (pinfunction "1_1") (pintype "passive"))
      (node (ref "XC9") (pin "L9") (pinfunction "L9_L9") (pintype "passive"))
    )
    (net (code "26") (name "/SFPP1_RxLOS") (class "Default")
      (node (ref "R185") (pin "1") (pinfunction "1_1") (pintype "passive"))
      (node (ref "XC9") (pin "L8") (pinfunction "L8_L8") (pintype "passive"))
    )
    (net (code "27") (name "/SFPP1_SCL") (class "Default")
      (node (ref "R187") (pin "1") (pinfunction "1_1") (pintype "passive"))
      (node (ref "XC9") (pin "L5") (pinfunction "L5_L5") (pintype "passive"))
    )
    (net (code "28") (name "/SFPP1_SDA") (class "Default")
      (node (ref "R193") (pin "1") (pinfunction "1_1") (pintype "passive"))
      (node (ref "XC9") (pin "L4") (pinfunction "L4_L4") (pintype "passive"))
    )
    (net (code "29") (name "/SFPP1_TxDisable") (class "Default")
      (node (ref "R195") (pin "1") (pinfunction "1_1") (pintype "passive"))
      (node (ref "XC9") (pin "L3") (pinfunction "L3_L3") (pintype "passive"))
    )
    (net (code "30") (name "/SFPP1_TxFault") (class "Default")
      (node (ref "R184") (pin "1") (pinfunction "1_1") (pintype "passive"))
      (node (ref "XC9") (pin "L2") (pinfunction "L2_L2") (pintype "passive"))
    )
    (net (code "31") (name "/SFPP2_ModAbs") (class "Default")
      (node (ref "R190") (pin "1") (pinfunction "1_1") (pintype "passive"))
      (node (ref "XC9") (pin "T6") (pinfunction "T6_T6") (pintype "passive"))
    )
    (net (code "32") (name "/SFPP2_RS0") (class "Default")
      (node (ref "R188") (pin "1") (pinfunction "1_1") (pintype "passive"))
      (node (ref "XC9") (pin "T7") (pinfunction "T7_T7") (pintype "passive"))
    )
    (net (code "33") (name "/SFPP2_RS1") (class "Default")
      (node (ref "R197") (pin "1") (pinfunction "1_1") (pintype "passive"))
      (node (ref "XC9") (pin "T9") (pinfunction "T9_T9") (pintype "passive"))
    )
    (net (code "34") (name "/SFPP2_RxLOS") (class "Default")
      (node (ref "R186") (pin "1") (pinfunction "1_1") (pintype "passive"))
      (node (ref "XC9") (pin "T8") (pinfunction "T8_T8") (pintype "passive"))
    )
    (net (code "35") (name "/SFPP2_SCL") (class "Default")
      (node (ref "R196") (pin "1") (pinfunction "1_1") (pintype "passive"))
      (node (ref "XC9") (pin "T5") (pinfunction "T5_T5") (pintype "passive"))
    )
    (net (code "36") (name "/SFPP2_SDA") (class "Default")
      (node (ref "R191") (pin "1") (pinfunction "1_1") (pintype "passive"))
      (node (ref "XC9") (pin "T4") (pinfunction "T4_T4") (pintype "passive"))
    )
    (net (code "37") (name "/SFPP2_TxDisable") (class "Default")
      (node (ref "R192") (pin "1") (pinfunction "1_1") (pintype "passive"))
      (node (ref "XC9") (pin "T3") (pinfunction "T3_T3") (pintype "passive"))
    )
    (net (code "38") (name "/SFPP2_TxFault") (class "Default")
      (node (ref "R198") (pin "1") (pinfunction "1_1") (pintype "passive"))
      (node (ref "XC9") (pin "T2") (pinfunction "T2_T2") (pintype "passive"))
    )
    (net (code "39") (name "3V3_MGT") (class "Default")
      (node (ref "C397") (pin "2") (pinfunction "2_2") (pintype "passive"))
      (node (ref "C398") (pin "1") (pinfunction "1_1") (pintype "passive"))
      (node (ref "C399") (pin "1") (pinfunction "1_1") (pintype "passive"))
      (node (ref "C400") (pin "2") (pinfunction "2_2") (pintype "passive"))
      (node (ref "C403") (pin "2") (pinfunction "2_2") (pintype "passive"))
      (node (ref "C404") (pin "2") (pinfunction "2_2") (pintype "passive"))
      (node (ref "C405") (pin "1") (pinfunction "1_1") (pintype "passive"))
      (node (ref "C406") (pin "1") (pinfunction "1_1") (pintype "passive"))
      (node (ref "L40") (pin "1") (pinfunction "1_1") (pintype "passive"))
      (node (ref "L41") (pin "2") (pinfunction "2_2") (pintype "passive"))
      (node (ref "L42") (pin "1") (pinfunction "1_1") (pintype "passive"))
      (node (ref "L43") (pin "2") (pinfunction "2_2") (pintype "passive"))
    )
    (net (code "40") (name "3V3_SFP+_CLK") (class "Default")
      (node (ref "C382") (pin "1") (pinfunction "1_1") (pintype "passive"))
      (node (ref "C383") (pin "1") (pinfunction "1_1") (pintype "passive"))
      (node (ref "L39") (pin "2") (pinfunction "2_2") (pintype "passive"))
    )
    (net (code "41") (name "5V") (class "Default")
      (node (ref "XC9") (pin "INL_2") (pinfunction "A_INL_2") (pintype "passive"))
      (node (ref "XC9") (pin "INR_2") (pinfunction "A_INR_2") (pintype "passive"))
      (node (ref "XC9") (pin "OUTL_2") (pinfunction "A_OUTL_2") (pintype "passive"))
      (node (ref "XC9") (pin "OUTR_2") (pinfunction "A_OUTR_2") (pintype "passive"))
    )
    (net (code "42") (name "DVDD_FPGA") (class "Default")
      (node (ref "R183") (pin "2") (pinfunction "2_2") (pintype "passive"))
      (node (ref "R184") (pin "2") (pinfunction "2_2") (pintype "passive"))
      (node (ref "R185") (pin "2") (pinfunction "2_2") (pintype "passive"))
      (node (ref "R186") (pin "2") (pinfunction "2_2") (pintype "passive"))
      (node (ref "R187") (pin "2") (pinfunction "2_2") (pintype "passive"))
      (node (ref "R188") (pin "2") (pinfunction "2_2") (pintype "passive"))
      (node (ref "R189") (pin "2") (pinfunction "2_2") (pintype "passive"))
      (node (ref "R190") (pin "2") (pinfunction "2_2") (pintype "passive"))
      (node (ref "R191") (pin "2") (pinfunction "2_2") (pintype "passive"))
      (node (ref "R192") (pin "2") (pinfunction "2_2") (pintype "passive"))
      (node (ref "R193") (pin "2") (pinfunction "2_2") (pintype "passive"))
      (node (ref "R194") (pin "2") (pinfunction "2_2") (pintype "passive"))
      (node (ref "R195") (pin "2") (pinfunction "2_2") (pintype "passive"))
      (node (ref "R196") (pin "2") (pinfunction "2_2") (pintype "passive"))
      (node (ref "R197") (pin "2") (pinfunction "2_2") (pintype "passive"))
      (node (ref "R198") (pin "2") (pinfunction "2_2") (pintype "passive"))
    )
    (net (code "43") (name "GND") (class "Default")
      (node (ref "C370") (pin "2") (pinfunction "2_2") (pintype "passive"))
      (node (ref "C371") (pin "1") (pinfunction "1_1") (pintype "passive"))
      (node (ref "C372") (pin "1") (pinfunction "1_1") (pintype "passive"))
      (node (ref "C373") (pin "2") (pinfunction "2_2") (pintype "passive"))
      (node (ref "C374") (pin "2") (pinfunction "2_2") (pintype "passive"))
      (node (ref "C375") (pin "2") (pinfunction "2_2") (pintype "passive"))
      (node (ref "C376") (pin "2") (pinfunction "2_2") (pintype "passive"))
      (node (ref "C377") (pin "2") (pinfunction "2_2") (pintype "passive"))
      (node (ref "C378") (pin "2") (pinfunction "2_2") (pintype "passive"))
      (node (ref "C379") (pin "1") (pinfunction "1_1") (pintype "passive"))
      (node (ref "C380") (pin "1") (pinfunction "1_1") (pintype "passive"))
      (node (ref "C381") (pin "2") (pinfunction "2_2") (pintype "passive"))
      (node (ref "C382") (pin "2") (pinfunction "2_2") (pintype "passive"))
      (node (ref "C383") (pin "2") (pinfunction "2_2") (pintype "passive"))
      (node (ref "C384") (pin "2") (pinfunction "2_2") (pintype "passive"))
      (node (ref "C385") (pin "2") (pinfunction "2_2") (pintype "passive"))
      (node (ref "C386") (pin "1") (pinfunction "1_1") (pintype "passive"))
      (node (ref "C387") (pin "1") (pinfunction "1_1") (pintype "passive"))
      (node (ref "C388") (pin "2") (pinfunction "2_2") (pintype "passive"))
      (node (ref "C389") (pin "1") (pinfunction "1_1") (pintype "passive"))
      (node (ref "C390") (pin "2") (pinfunction "2_2") (pintype "passive"))
      (node (ref "C391") (pin "2") (pinfunction "2_2") (pintype "passive"))
      (node (ref "C392") (pin "1") (pinfunction "1_1") (pintype "passive"))
      (node (ref "C393") (pin "2") (pinfunction "2_2") (pintype "passive"))
      (node (ref "C394") (pin "2") (pinfunction "2_2") (pintype "passive"))
      (node (ref "C395") (pin "2") (pinfunction "2_2") (pintype "passive"))
      (node (ref "C396") (pin "2") (pinfunction "2_2") (pintype "passive"))
      (node (ref "C397") (pin "1") (pinfunction "1_1") (pintype "passive"))
      (node (ref "C398") (pin "2") (pinfunction "2_2") (pintype "passive"))
      (node (ref "C399") (pin "2") (pinfunction "2_2") (pintype "passive"))
      (node (ref "C400") (pin "1") (pinfunction "1_1") (pintype "passive"))
      (node (ref "C401") (pin "2") (pinfunction "2_2") (pintype "passive"))
      (node (ref "C402") (pin "2") (pinfunction "2_2") (pintype "passive"))
      (node (ref "C403") (pin "1") (pinfunction "1_1") (pintype "passive"))
      (node (ref "C404") (pin "1") (pinfunction "1_1") (pintype "passive"))
      (node (ref "C405") (pin "2") (pinfunction "2_2") (pintype "passive"))
      (node (ref "C406") (pin "2") (pinfunction "2_2") (pintype "passive"))
      (node (ref "C407") (pin "2") (pinfunction "2_2") (pintype "passive"))
      (node (ref "C408") (pin "2") (pinfunction "2_2") (pintype "passive"))
      (node (ref "C409") (pin "2") (pinfunction "2_2") (pintype "passive"))
      (node (ref "C410") (pin "2") (pinfunction "2_2") (pintype "passive"))
      (node (ref "C415") (pin "1") (pinfunction "1_1") (pintype "passive"))
      (node (ref "C416") (pin "1") (pinfunction "1_1") (pintype "passive"))
      (node (ref "CXO3") (pin "3") (pinfunction "GND_3") (pintype "power_in"))
      (node (ref "CXO4") (pin "3") (pinfunction "GND_3") (pintype "power_in"))
      (node (ref "FPGA1") (pin "A13") (pinfunction "MGTPRXN2_216_A13") (pintype "input"))
      (node (ref "FPGA1") (pin "AC14") (pinfunction "MGTPRXP2_213_AC14") (pintype "input"))
      (node (ref "FPGA1") (pin "AD14") (pinfunction "MGTPRXN2_213_AD14") (pintype "input"))
      (node (ref "FPGA1") (pin "AE11") (pinfunction "MGTPRXP3_213_AE11") (pintype "input"))
      (node (ref "FPGA1") (pin "AE13") (pinfunction "MGTPRXP1_213_AE13") (pintype "input"))
      (node (ref "FPGA1") (pin "AF11") (pinfunction "MGTPRXN3_213_AF11") (pintype "input"))
      (node (ref "FPGA1") (pin "AF13") (pinfunction "MGTPRXN1_213_AF13") (pintype "input"))
      (node (ref "FPGA1") (pin "B13") (pinfunction "MGTPRXP2_216_B13") (pintype "input"))
      (node (ref "FPGA1") (pin "C12") (pinfunction "MGTPRXN3_216_C12") (pintype "input"))
      (node (ref "FPGA1") (pin "C14") (pinfunction "MGTPRXN1_216_C14") (pintype "input"))
      (node (ref "FPGA1") (pin "D12") (pinfunction "MGTPRXP3_216_D12") (pintype "input"))
      (node (ref "FPGA1") (pin "D14") (pinfunction "MGTPRXP1_216_D14") (pintype "input"))
      (node (ref "Q14") (pin "2") (pinfunction "S_2") (pintype "passive"))
      (node (ref "Q15") (pin "2") (pinfunction "S_2") (pintype "passive"))
      (node (ref "Q16") (pin "2") (pinfunction "S_2") (pintype "passive"))
      (node (ref "Q17") (pin "2") (pinfunction "S_2") (pintype "passive"))
      (node (ref "R211") (pin "1") (pinfunction "1_1") (pintype "passive"))
      (node (ref "R212") (pin "1") (pinfunction "1_1") (pintype "passive"))
      (node (ref "R213") (pin "1") (pinfunction "1_1") (pintype "passive"))
      (node (ref "R214") (pin "1") (pinfunction "1_1") (pintype "passive"))
      (node (ref "R228") (pin "2") (pinfunction "2_2") (pintype "passive"))
      (node (ref "R229") (pin "2") (pinfunction "2_2") (pintype "passive"))
      (node (ref "R230") (pin "2") (pinfunction "2_2") (pintype "passive"))
      (node (ref "R231") (pin "2") (pinfunction "2_2") (pintype "passive"))
      (node (ref "XC9") (pin "0") (pinfunction "M_0") (pintype "passive"))
      (node (ref "XC9") (pin "L1") (pinfunction "L1_L1") (pintype "passive"))
      (node (ref "XC9") (pin "L10") (pinfunction "L10_L10") (pintype "passive"))
      (node (ref "XC9") (pin "L11") (pinfunction "L11_L11") (pintype "passive"))
      (node (ref "XC9") (pin "L14") (pinfunction "L14_L14") (pintype "passive"))
      (node (ref "XC9") (pin "L17") (pinfunction "L17_L17") (pintype "passive"))
      (node (ref "XC9") (pin "L20") (pinfunction "L20_L20") (pintype "passive"))
      (node (ref "XC9") (pin "T1") (pinfunction "T1_T1") (pintype "passive"))
      (node (ref "XC9") (pin "T10") (pinfunction "T10_T10") (pintype "passive"))
      (node (ref "XC9") (pin "T11") (pinfunction "T11_T11") (pintype "passive"))
      (node (ref "XC9") (pin "T14") (pinfunction "T14_T14") (pintype "passive"))
      (node (ref "XC9") (pin "T17") (pinfunction "T17_T17") (pintype "passive"))
      (node (ref "XC9") (pin "T20") (pinfunction "T20_T20") (pintype "passive"))
    )
    (net (code "44") (name "Net-(C411-Pad1)") (class "Default")
      (node (ref "C411") (pin "1") (pinfunction "1_1") (pintype "passive"))
      (node (ref "R208") (pin "1") (pinfunction "1_1") (pintype "passive"))
    )
    (net (code "45") (name "Net-(C412-Pad1)") (class "Default")
      (node (ref "C412") (pin "1") (pinfunction "1_1") (pintype "passive"))
      (node (ref "R204") (pin "1") (pinfunction "1_1") (pintype "passive"))
    )
    (net (code "46") (name "Net-(C413-Pad1)") (class "Default")
      (node (ref "C413") (pin "1") (pinfunction "1_1") (pintype "passive"))
      (node (ref "R207") (pin "1") (pinfunction "1_1") (pintype "passive"))
    )
    (net (code "47") (name "Net-(C414-Pad1)") (class "Default")
      (node (ref "C414") (pin "1") (pinfunction "1_1") (pintype "passive"))
      (node (ref "R203") (pin "1") (pinfunction "1_1") (pintype "passive"))
    )
    (net (code "48") (name "Net-(CXO3-Enable)") (class "Default")
      (node (ref "CXO3") (pin "1") (pinfunction "Enable_1") (pintype "input"))
      (node (ref "R209") (pin "2") (pinfunction "2_2") (pintype "passive"))
    )
    (net (code "49") (name "Net-(CXO3-OUTN)") (class "Default")
      (node (ref "C411") (pin "2") (pinfunction "2_2") (pintype "passive"))
      (node (ref "CXO3") (pin "5") (pinfunction "OUTN_5") (pintype "output"))
      (node (ref "R211") (pin "2") (pinfunction "2_2") (pintype "passive"))
    )
    (net (code "50") (name "Net-(CXO3-OUTP)") (class "Default")
      (node (ref "C413") (pin "2") (pinfunction "2_2") (pintype "passive"))
      (node (ref "CXO3") (pin "4") (pinfunction "OUTP_4") (pintype "output"))
      (node (ref "R212") (pin "2") (pinfunction "2_2") (pintype "passive"))
    )
    (net (code "51") (name "Net-(CXO3-VDD)") (class "Default")
      (node (ref "C409") (pin "1") (pinfunction "1_1") (pintype "passive"))
      (node (ref "CXO3") (pin "6") (pinfunction "VDD_6") (pintype "power_in"))
      (node (ref "L44") (pin "2") (pinfunction "2_2") (pintype "passive"))
    )
    (net (code "52") (name "Net-(CXO4-Enable)") (class "Default")
      (node (ref "CXO4") (pin "1") (pinfunction "Enable_1") (pintype "input"))
      (node (ref "R210") (pin "2") (pinfunction "2_2") (pintype "passive"))
    )
    (net (code "53") (name "Net-(CXO4-OUTN)") (class "Default")
      (node (ref "C412") (pin "2") (pinfunction "2_2") (pintype "passive"))
      (node (ref "CXO4") (pin "5") (pinfunction "OUTN_5") (pintype "output"))
      (node (ref "R213") (pin "2") (pinfunction "2_2") (pintype "passive"))
    )
    (net (code "54") (name "Net-(CXO4-OUTP)") (class "Default")
      (node (ref "C414") (pin "2") (pinfunction "2_2") (pintype "passive"))
      (node (ref "CXO4") (pin "4") (pinfunction "OUTP_4") (pintype "output"))
      (node (ref "R214") (pin "2") (pinfunction "2_2") (pintype "passive"))
    )
    (net (code "55") (name "Net-(CXO4-VDD)") (class "Default")
      (node (ref "C410") (pin "1") (pinfunction "1_1") (pintype "passive"))
      (node (ref "CXO4") (pin "6") (pinfunction "VDD_6") (pintype "power_in"))
      (node (ref "L45") (pin "2") (pinfunction "2_2") (pintype "passive"))
    )
    (net (code "56") (name "Net-(FPGA1J-MGTRREF_213)") (class "Default")
      (node (ref "FPGA1") (pin "AF15") (pinfunction "MGTRREF_213_AF15") (pintype "input"))
      (node (ref "R215") (pin "2") (pinfunction "2_2") (pintype "passive"))
    )
    (net (code "57") (name "Net-(FPGA1J-MGTRREF_216)") (class "Default")
      (node (ref "FPGA1") (pin "A15") (pinfunction "MGTRREF_216_A15") (pintype "input"))
      (node (ref "R216") (pin "2") (pinfunction "2_2") (pintype "passive"))
    )
    (net (code "58") (name "Net-(Q14-D)") (class "Default")
      (node (ref "Q14") (pin "3") (pinfunction "D_3") (pintype "passive"))
      (node (ref "R199") (pin "1") (pinfunction "1_1") (pintype "passive"))
    )
    (net (code "59") (name "Net-(Q15-D)") (class "Default")
      (node (ref "Q15") (pin "3") (pinfunction "D_3") (pintype "passive"))
      (node (ref "R200") (pin "2") (pinfunction "2_2") (pintype "passive"))
    )
    (net (code "60") (name "Net-(Q16-D)") (class "Default")
      (node (ref "Q16") (pin "3") (pinfunction "D_3") (pintype "passive"))
      (node (ref "R201") (pin "1") (pinfunction "1_1") (pintype "passive"))
    )
    (net (code "61") (name "Net-(Q17-D)") (class "Default")
      (node (ref "Q17") (pin "3") (pinfunction "D_3") (pintype "passive"))
      (node (ref "R202") (pin "2") (pinfunction "2_2") (pintype "passive"))
    )
    (net (code "62") (name "Net-(R199-Pad2)") (class "Default")
      (node (ref "R199") (pin "2") (pinfunction "2_2") (pintype "passive"))
      (node (ref "XC9") (pin "INL_1") (pinfunction "K_INL_1") (pintype "passive"))
    )
    (net (code "63") (name "Net-(R200-Pad1)") (class "Default")
      (node (ref "R200") (pin "1") (pinfunction "1_1") (pintype "passive"))
      (node (ref "XC9") (pin "INR_1") (pinfunction "K_INR_1") (pintype "passive"))
    )
    (net (code "64") (name "Net-(R201-Pad2)") (class "Default")
      (node (ref "R201") (pin "2") (pinfunction "2_2") (pintype "passive"))
      (node (ref "XC9") (pin "OUTL_1") (pinfunction "K_OUTL_1") (pintype "passive"))
    )
    (net (code "65") (name "Net-(R202-Pad1)") (class "Default")
      (node (ref "R202") (pin "1") (pinfunction "1_1") (pintype "passive"))
      (node (ref "XC9") (pin "OUTR_1") (pinfunction "K_OUTR_1") (pintype "passive"))
    )
    (net (code "66") (name "SFP+_CLK_VCC") (class "Default")
      (node (ref "C384") (pin "1") (pinfunction "1_1") (pintype "passive"))
      (node (ref "C385") (pin "1") (pinfunction "1_1") (pintype "passive"))
      (node (ref "C386") (pin "2") (pinfunction "2_2") (pintype "passive"))
      (node (ref "C415") (pin "2") (pinfunction "2_2") (pintype "passive"))
      (node (ref "C416") (pin "2") (pinfunction "2_2") (pintype "passive"))
      (node (ref "L39") (pin "1") (pinfunction "1_1") (pintype "passive"))
      (node (ref "L44") (pin "1") (pinfunction "1_1") (pintype "passive"))
      (node (ref "L45") (pin "1") (pinfunction "1_1") (pintype "passive"))
      (node (ref "R209") (pin "1") (pinfunction "1_1") (pintype "passive"))
      (node (ref "R210") (pin "1") (pinfunction "1_1") (pintype "passive"))
    )
    (net (code "67") (name "SFP1_VccRX") (class "Default")
      (node (ref "C407") (pin "1") (pinfunction "1_1") (pintype "passive"))
      (node (ref "L42") (pin "2") (pinfunction "2_2") (pintype "passive"))
      (node (ref "XC9") (pin "L15") (pinfunction "L15_L15") (pintype "passive"))
    )
    (net (code "68") (name "SFP1_VccTX") (class "Default")
      (node (ref "C401") (pin "1") (pinfunction "1_1") (pintype "passive"))
      (node (ref "L40") (pin "2") (pinfunction "2_2") (pintype "passive"))
      (node (ref "XC9") (pin "L16") (pinfunction "L16_L16") (pintype "passive"))
    )
    (net (code "69") (name "SFP2_VccRX") (class "Default")
      (node (ref "C408") (pin "1") (pinfunction "1_1") (pintype "passive"))
      (node (ref "L43") (pin "1") (pinfunction "1_1") (pintype "passive"))
      (node (ref "XC9") (pin "T15") (pinfunction "T15_T15") (pintype "passive"))
    )
    (net (code "70") (name "SFP2_VccTX") (class "Default")
      (node (ref "C402") (pin "1") (pinfunction "1_1") (pintype "passive"))
      (node (ref "L41") (pin "1") (pinfunction "1_1") (pintype "passive"))
      (node (ref "XC9") (pin "T16") (pinfunction "T16_T16") (pintype "passive"))
    )
    (net (code "71") (name "unconnected-(CXO3-NC-Pad2)") (class "Default")
      (node (ref "CXO3") (pin "2") (pinfunction "NC_2") (pintype "passive"))
    )
    (net (code "72") (name "unconnected-(CXO4-NC-Pad2)") (class "Default")
      (node (ref "CXO4") (pin "2") (pinfunction "NC_2") (pintype "passive"))
    )
    (net (code "73") (name "unconnected-(FPGA1J-MGTPTXN1_213-PadAF9)") (class "Default")
      (node (ref "FPGA1") (pin "AF9") (pinfunction "MGTPTXN1_213_AF9") (pintype "output+no_connect"))
    )
    (net (code "74") (name "unconnected-(FPGA1J-MGTPTXN1_216-PadC8)") (class "Default")
      (node (ref "FPGA1") (pin "C8") (pinfunction "MGTPTXN1_216_C8") (pintype "output+no_connect"))
    )
    (net (code "75") (name "unconnected-(FPGA1J-MGTPTXN2_213-PadAD8)") (class "Default")
      (node (ref "FPGA1") (pin "AD8") (pinfunction "MGTPTXN2_213_AD8") (pintype "output+no_connect"))
    )
    (net (code "76") (name "unconnected-(FPGA1J-MGTPTXN2_216-PadA9)") (class "Default")
      (node (ref "FPGA1") (pin "A9") (pinfunction "MGTPTXN2_216_A9") (pintype "output+no_connect"))
    )
    (net (code "77") (name "unconnected-(FPGA1J-MGTPTXN3_213-PadAF7)") (class "Default")
      (node (ref "FPGA1") (pin "AF7") (pinfunction "MGTPTXN3_213_AF7") (pintype "output+no_connect"))
    )
    (net (code "78") (name "unconnected-(FPGA1J-MGTPTXN3_216-PadC10)") (class "Default")
      (node (ref "FPGA1") (pin "C10") (pinfunction "MGTPTXN3_216_C10") (pintype "output+no_connect"))
    )
    (net (code "79") (name "unconnected-(FPGA1J-MGTPTXP1_213-PadAE9)") (class "Default")
      (node (ref "FPGA1") (pin "AE9") (pinfunction "MGTPTXP1_213_AE9") (pintype "output+no_connect"))
    )
    (net (code "80") (name "unconnected-(FPGA1J-MGTPTXP1_216-PadD8)") (class "Default")
      (node (ref "FPGA1") (pin "D8") (pinfunction "MGTPTXP1_216_D8") (pintype "output+no_connect"))
    )
    (net (code "81") (name "unconnected-(FPGA1J-MGTPTXP2_213-PadAC8)") (class "Default")
      (node (ref "FPGA1") (pin "AC8") (pinfunction "MGTPTXP2_213_AC8") (pintype "output+no_connect"))
    )
    (net (code "82") (name "unconnected-(FPGA1J-MGTPTXP2_216-PadB9)") (class "Default")
      (node (ref "FPGA1") (pin "B9") (pinfunction "MGTPTXP2_216_B9") (pintype "output+no_connect"))
    )
    (net (code "83") (name "unconnected-(FPGA1J-MGTPTXP3_213-PadAE7)") (class "Default")
      (node (ref "FPGA1") (pin "AE7") (pinfunction "MGTPTXP3_213_AE7") (pintype "output+no_connect"))
    )
    (net (code "84") (name "unconnected-(FPGA1J-MGTPTXP3_216-PadD10)") (class "Default")
      (node (ref "FPGA1") (pin "D10") (pinfunction "MGTPTXP3_216_D10") (pintype "output+no_connect"))
    )
    (net (code "85") (name "unconnected-(FPGA1J-MGTREFCLK1N_216-PadE13)") (class "Default")
      (node (ref "FPGA1") (pin "E13") (pinfunction "MGTREFCLK1N_216_E13") (pintype "input+no_connect"))
    )
    (net (code "86") (name "unconnected-(FPGA1J-MGTREFCLK1P_216-PadF13)") (class "Default")
      (node (ref "FPGA1") (pin "F13") (pinfunction "MGTREFCLK1P_216_F13") (pintype "input+no_connect"))
    )
  )
)
